# AMU-S03-V00-PSU3V5.net
KiCad netlist of a schematic drawn in Altium Designer
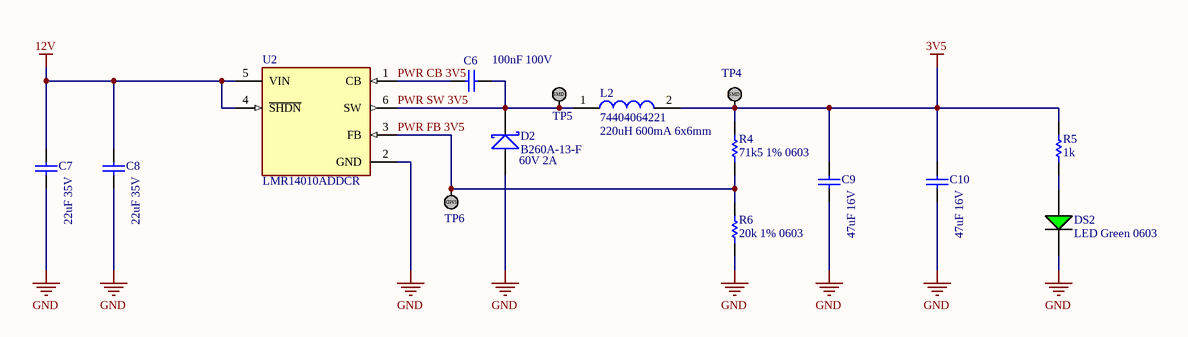
[diagram p0: AMU-S03-V00-PSU3V5.SchDoc]

(export (version "E")
  (design (tool "Eeschema 10.0.6"))
  (components
    (comp (ref "C6")
      (value "100nF 100V")
      (footprint "Cap_Ceramic_0603")
      (description "Capacitor, Ceramic, SMD, 100nF, 100V, 5%, X7R, 0603")
      (libsource (lib "StandardCapacitors") (part "100nF 100V 5% X7R 0603"))
    )
    (comp (ref "C7")
      (value "22uF 35V")
      (footprint "Cap_Ceramic_1206")
      (description "22µF ±20% 35V Ceramic Capacitor X5R 1206 (3216 Metric)")
      (libsource (lib "StandardCapacitors") (part "22uF 35V 20% X5R 1206"))
    )
    (comp (ref "C8")
      (value "22uF 35V")
      (footprint "Cap_Ceramic_1206")
      (description "22µF ±20% 35V Ceramic Capacitor X5R 1206 (3216 Metric)")
      (libsource (lib "StandardCapacitors") (part "22uF 35V 20% X5R 1206"))
    )
    (comp (ref "C9")
      (value "47uF 16V")
      (footprint "Cap_Ceramic_0603")
      (description "Capacitor, Ceramic, SMD, 47uF, 16V, 5%, X7R, 1210")
      (libsource (lib "StandardCapacitors") (part "47uF 16V 10% X7R 1210"))
    )
    (comp (ref "C10")
      (value "47uF 16V")
      (footprint "Cap_Ceramic_0603")
      (description "Capacitor, Ceramic, SMD, 47uF, 16V, 5%, X7R, 1210")
      (libsource (lib "StandardCapacitors") (part "47uF 16V 10% X7R 1210"))
    )
    (comp (ref "D2")
      (value "B260A-13-F")
      (footprint "SMA")
      (description "Diode, Schottky Barrier Rectifier, 60 V, 2 A, B260A-13-F")
      (libsource (lib "QUTMS_DiodeLibrary") (part "B260A-13-F"))
    )
    (comp (ref "DS2")
      (value "LED Green 0603")
      (footprint "LED GREEN 0603")
      (libsource (lib "QUTMS_LEDLibrary") (part "LED Green 0603"))
    )
    (comp (ref "L2")
      (value "74404064221")
      (footprint "Inductor_6x6mm")
      (description "FIXED IND 220UH 660MA 850 MOHM")
      (libsource (lib "QUTMS_InductorLibrary") (part "74404064221"))
    )
    (comp (ref "R4")
      (value "71k5 1% 0603")
      (footprint "Res_ThinFilm_0603")
      (description "Resistor, SMD, 71k5, 0.1W, 1%, 0603")
      (libsource (lib "StandardResistors") (part "71k5 1% 0603"))
    )
    (comp (ref "R5")
      (value "1k")
      (footprint "Res_ThinFilm_0603")
      (description "Resistor, SMD, 1k, 0.1W, 5%, 0603")
      (libsource (lib "StandardResistors") (part "1k 5% 0603"))
    )
    (comp (ref "R6")
      (value "20k 1% 0603")
      (footprint "Res_ThinFilm_0603")
      (description "Resistor, SMD, 20k, 0.1W, 1%, 0603")
      (libsource (lib "StandardResistors") (part "20k 1% 0603"))
    )
    (comp (ref "TP4")
      (value "TestPoint_SMD")
      (footprint "TestPointSMD")
      (libsource (lib "StandardTest") (part "TestPoint_SMD"))
    )
    (comp (ref "TP5")
      (value "TestPoint_SMD")
      (footprint "TestPointSMD")
      (libsource (lib "StandardTest") (part "TestPoint_SMD"))
    )
    (comp (ref "TP6")
      (value "TestPoint_SMD")
      (footprint "TestPointSMD")
      (libsource (lib "StandardTest") (part "TestPoint_SMD"))
    )
    (comp (ref "U2")
      (value "LMR14010ADDCR")
      (footprint "FP-DDC0006A-MFG")
      (description "IC REG BUCK ADJ 1A TSOT23-6")
      (fields
        (field (name "MANUFACTURER") "Texas Instruments")
        (field (name "OCTOPART") "https://octopart.com/lmr14010addcr-texas+instruments-90753290")
      )
      (libsource (lib "Altium Content Vault") (part "248534993f007311ab4e1890f26e637"))
    )
  )
  (nets
    (net (code "1") (name "/PWR CB 3V5") (class "Default")
      (node (ref "C6") (pin "1") (pinfunction "1_1") (pintype "passive"))
      (node (ref "U2") (pin "1") (pinfunction "CB_1") (pintype "input"))
    )
    (net (code "2") (name "/PWR FB 3V5") (class "Default")
      (node (ref "R4") (pin "1") (pinfunction "1_1") (pintype "passive"))
      (node (ref "R6") (pin "2") (pinfunction "2_2") (pintype "passive"))
      (node (ref "TP6") (pin "1") (pinfunction "1_1") (pintype "passive"))
      (node (ref "U2") (pin "3") (pinfunction "FB_3") (pintype "input"))
    )
    (net (code "3") (name "/PWR SW 3V5") (class "Default")
      (node (ref "C6") (pin "2") (pinfunction "2_2") (pintype "passive"))
      (node (ref "D2") (pin "K") (pinfunction "K_K") (pintype "passive"))
      (node (ref "L2") (pin "1") (pinfunction "1_1") (pintype "passive"))
      (node (ref "TP5") (pin "1") (pinfunction "1_1") (pintype "passive"))
      (node (ref "U2") (pin "6") (pinfunction "SW_6") (pintype "output"))
    )
    (net (code "4") (name "3V5") (class "Default")
      (node (ref "C10") (pin "2") (pinfunction "2_2") (pintype "passive"))
      (node (ref "C9") (pin "2") (pinfunction "2_2") (pintype "passive"))
      (node (ref "L2") (pin "2") (pinfunction "2_2") (pintype "passive"))
      (node (ref "R4") (pin "2") (pinfunction "2_2") (pintype "passive"))
      (node (ref "R5") (pin "2") (pinfunction "2_2") (pintype "passive"))
      (node (ref "TP4") (pin "1") (pinfunction "1_1") (pintype "passive"))
    )
    (net (code "5") (name "12V") (class "Default")
      (node (ref "C7") (pin "2") (pinfunction "2_2") (pintype "passive"))
      (node (ref "C8") (pin "2") (pinfunction "2_2") (pintype "passive"))
      (node (ref "U2") (pin "4") (pinfunction "~{SHDN}_4") (pintype "input"))
      (node (ref "U2") (pin "5") (pinfunction "VIN_5") (pintype "power_in"))
    )
    (net (code "6") (name "GND") (class "Default")
      (node (ref "C10") (pin "1") (pinfunction "1_1") (pintype "passive"))
      (node (ref "C7") (pin "1") (pinfunction "1_1") (pintype "passive"))
      (node (ref "C8") (pin "1") (pinfunction "1_1") (pintype "passive"))
      (node (ref "C9") (pin "1") (pinfunction "1_1") (pintype "passive"))
      (node (ref "D2") (pin "A") (pinfunction "A_A") (pintype "passive"))
      (node (ref "DS2") (pin "2") (pinfunction "C_2") (pintype "passive"))
      (node (ref "R6") (pin "1") (pinfunction "1_1") (pintype "passive"))
      (node (ref "U2") (pin "2") (pinfunction "GND_2") (pintype "power_in"))
    )
    (net (code "7") (name "Net-(DS2-A)") (class "Default")
      (node (ref "DS2") (pin "1") (pinfunction "A_1") (pintype "passive"))
      (node (ref "R5") (pin "1") (pinfunction "1_1") (pintype "passive"))
    )
  )
)
